# PS.net
KiCad netlist of a schematic drawn in EAGLE
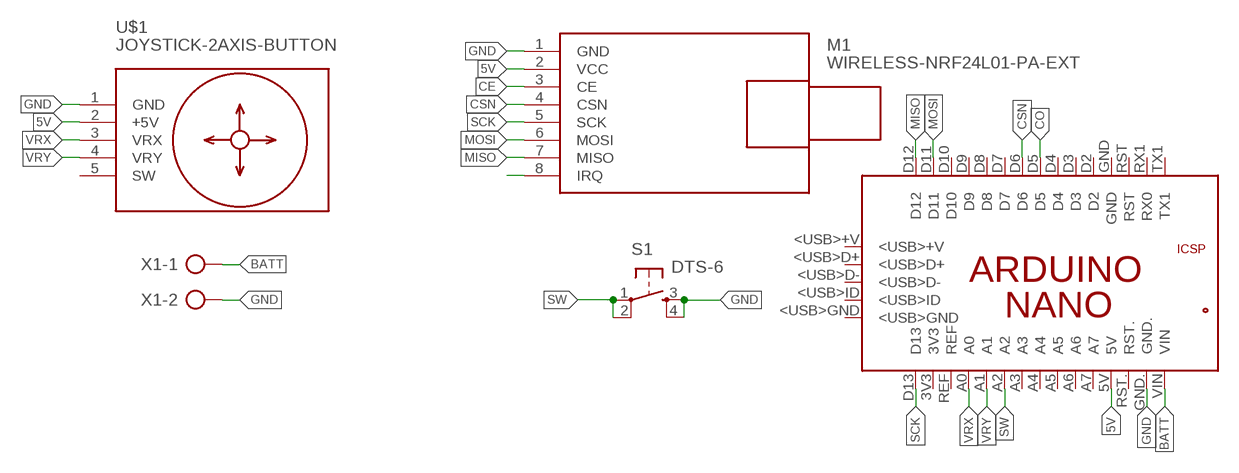
[diagram p0: schematic, sheet 1]

(export (version "E")
  (design (tool "Eeschema 10.0.6"))
  (components
    (comp (ref "M1")
      (value "WIRELESS-NRF24L01-PA-EXT")
      (footprint "eagle-import:WIRELESS-NRF24L01-PA-EXT")
      (libsource (lib "eagle-import") (part "WIRELESS-NRF24L01-PA-EXT"))
    )
    (comp (ref "PCB2")
      (value "ARDUINO_NANO")
      (footprint "eagle-import:ARDUINO_NANO")
      (libsource (lib "eagle-import") (part "ARDUINO_NANO"))
    )
    (comp (ref "S1")
      (value "DTS-6")
      (footprint "eagle-import:DTS-6")
      (libsource (lib "eagle-import") (part "DTS-6"))
    )
    (comp (ref "U$1")
      (value "JOYSTICK-2AXIS-BUTTON")
      (footprint "eagle-import:JOYSTICK-2AXIS-BUTTON")
      (libsource (lib "eagle-import") (part "JOYSTICK-2AXIS-BUTTON"))
    )
    (comp (ref "X1")
      (value "AK300/2")
      (footprint "eagle-import:AK300_2")
      (libsource (lib "eagle-import") (part "AK300/2"))
    )
  )
  (nets
    (net (code "1") (name "5V") (class "Default")
      (node (ref "M1") (pin "2") (pinfunction "VCC_2") (pintype "power_in"))
      (node (ref "PCB2") (pin "5V") (pinfunction "5V_5V") (pintype "bidirectional"))
      (node (ref "U$1") (pin "2") (pinfunction "+5V_2") (pintype "power_in"))
    )
    (net (code "2") (name "BATT") (class "Default")
      (node (ref "PCB2") (pin "VIN") (pinfunction "VIN_VIN") (pintype "bidirectional"))
      (node (ref "X1") (pin "1") (pinfunction "KL_1") (pintype "passive"))
    )
    (net (code "3") (name "CE") (class "Default")
      (node (ref "M1") (pin "3") (pinfunction "CE_3") (pintype "bidirectional"))
    )
    (net (code "4") (name "CO") (class "Default")
      (node (ref "PCB2") (pin "D5") (pinfunction "D5_D5") (pintype "bidirectional"))
    )
    (net (code "5") (name "CSN") (class "Default")
      (node (ref "M1") (pin "4") (pinfunction "CSN_4") (pintype "bidirectional"))
      (node (ref "PCB2") (pin "D6") (pinfunction "D6_D6") (pintype "bidirectional"))
    )
    (net (code "6") (name "GND") (class "Default")
      (node (ref "M1") (pin "1") (pinfunction "GND_1") (pintype "power_in"))
      (node (ref "PCB2") (pin "GND.") (pinfunction "GND._GND.") (pintype "bidirectional"))
      (node (ref "S1") (pin "3") (pinfunction "3_3") (pintype "passive"))
      (node (ref "S1") (pin "4") (pinfunction "4_4") (pintype "passive"))
      (node (ref "U$1") (pin "1") (pinfunction "GND_1") (pintype "power_in"))
      (node (ref "X1") (pin "2") (pinfunction "KL_2") (pintype "passive"))
    )
    (net (code "7") (name "MISO") (class "Default")
      (node (ref "M1") (pin "7") (pinfunction "MISO_7") (pintype "bidirectional"))
      (node (ref "PCB2") (pin "D12") (pinfunction "D12_D12") (pintype "bidirectional"))
    )
    (net (code "8") (name "MOSI") (class "Default")
      (node (ref "M1") (pin "6") (pinfunction "MOSI_6") (pintype "bidirectional"))
      (node (ref "PCB2") (pin "D11") (pinfunction "D11_D11") (pintype "bidirectional"))
    )
    (net (code "9") (name "SCK") (class "Default")
      (node (ref "M1") (pin "5") (pinfunction "SCK_5") (pintype "bidirectional"))
      (node (ref "PCB2") (pin "D13") (pinfunction "D13_D13") (pintype "bidirectional"))
    )
    (net (code "10") (name "SW") (class "Default")
      (node (ref "PCB2") (pin "A2") (pinfunction "A2_A2") (pintype "bidirectional"))
      (node (ref "S1") (pin "1") (pinfunction "1_1") (pintype "passive"))
      (node (ref "S1") (pin "2") (pinfunction "2_2") (pintype "passive"))
    )
    (net (code "11") (name "VRX") (class "Default")
      (node (ref "PCB2") (pin "A0") (pinfunction "A0_A0") (pintype "bidirectional"))
      (node (ref "U$1") (pin "3") (pinfunction "VRX_3") (pintype "passive"))
    )
    (net (code "12") (name "VRY") (class "Default")
      (node (ref "PCB2") (pin "A1") (pinfunction "A1_A1") (pintype "bidirectional"))
      (node (ref "U$1") (pin "4") (pinfunction "VRY_4") (pintype "passive"))
    )
    (net (code "13") (name "unconnected-(M1-IRQ-Pad8)") (class "Default")
      (node (ref "M1") (pin "8") (pinfunction "IRQ_8") (pintype "bidirectional"))
    )
    (net (code "14") (name "unconnected-(PCB2-Pad3V3)") (class "Default")
      (node (ref "PCB2") (pin "3V3") (pinfunction "3V3_3V3") (pintype "bidirectional"))
    )
    (net (code "15") (name "unconnected-(PCB2-Pad5V.)") (class "Default")
      (node (ref "PCB2") (pin "5V.") (pinfunction "5V._5V.") (pintype "bidirectional"))
    )
    (net (code "16") (name "unconnected-(PCB2-Pad<USB>+V)") (class "Default")
      (node (ref "PCB2") (pin "<USB>+V") (pinfunction "<USB>+V_<USB>+V") (pintype "bidirectional"))
    )
    (net (code "17") (name "unconnected-(PCB2-Pad<USB>D+)") (class "Default")
      (node (ref "PCB2") (pin "<USB>D+") (pinfunction "<USB>D+_<USB>D+") (pintype "bidirectional"))
    )
    (net (code "18") (name "unconnected-(PCB2-Pad<USB>D-)") (class "Default")
      (node (ref "PCB2") (pin "<USB>D-") (pinfunction "<USB>D-_<USB>D-") (pintype "bidirectional"))
    )
    (net (code "19") (name "unconnected-(PCB2-Pad<USB>GND)") (class "Default")
      (node (ref "PCB2") (pin "<USB>GND") (pinfunction "<USB>GND_<USB>GND") (pintype "bidirectional"))
    )
    (net (code "20") (name "unconnected-(PCB2-Pad<USB>ID)") (class "Default")
      (node (ref "PCB2") (pin "<USB>ID") (pinfunction "<USB>ID_<USB>ID") (pintype "bidirectional"))
    )
    (net (code "21") (name "unconnected-(PCB2-PadA3)") (class "Default")
      (node (ref "PCB2") (pin "A3") (pinfunction "A3_A3") (pintype "bidirectional"))
    )
    (net (code "22") (name "unconnected-(PCB2-PadA4)") (class "Default")
      (node (ref "PCB2") (pin "A4") (pinfunction "A4_A4") (pintype "bidirectional"))
    )
    (net (code "23") (name "unconnected-(PCB2-PadA5)") (class "Default")
      (node (ref "PCB2") (pin "A5") (pinfunction "A5_A5") (pintype "bidirectional"))
    )
    (net (code "24") (name "unconnected-(PCB2-PadA6)") (class "Default")
      (node (ref "PCB2") (pin "A6") (pinfunction "A6_A6") (pintype "bidirectional"))
    )
    (net (code "25") (name "unconnected-(PCB2-PadA7)") (class "Default")
      (node (ref "PCB2") (pin "A7") (pinfunction "A7_A7") (pintype "bidirectional"))
    )
    (net (code "26") (name "unconnected-(PCB2-PadD2)") (class "Default")
      (node (ref "PCB2") (pin "D2") (pinfunction "D2_D2") (pintype "bidirectional"))
    )
    (net (code "27") (name "unconnected-(PCB2-PadD3)") (class "Default")
      (node (ref "PCB2") (pin "D3") (pinfunction "D3_D3") (pintype "bidirectional"))
    )
    (net (code "28") (name "unconnected-(PCB2-PadD4)") (class "Default")
      (node (ref "PCB2") (pin "D4") (pinfunction "D4_D4") (pintype "bidirectional"))
    )
    (net (code "29") (name "unconnected-(PCB2-PadD7)") (class "Default")
      (node (ref "PCB2") (pin "D7") (pinfunction "D7_D7") (pintype "bidirectional"))
    )
    (net (code "30") (name "unconnected-(PCB2-PadD8)") (class "Default")
      (node (ref "PCB2") (pin "D8") (pinfunction "D8_D8") (pintype "bidirectional"))
    )
    (net (code "31") (name "unconnected-(PCB2-PadD9)") (class "Default")
      (node (ref "PCB2") (pin "D9") (pinfunction "D9_D9") (pintype "bidirectional"))
    )
    (net (code "32") (name "unconnected-(PCB2-PadD10)") (class "Default")
      (node (ref "PCB2") (pin "D10") (pinfunction "D10_D10") (pintype "bidirectional"))
    )
    (net (code "33") (name "unconnected-(PCB2-PadGND)") (class "Default")
      (node (ref "PCB2") (pin "GND") (pinfunction "GND_GND") (pintype "bidirectional"))
    )
    (net (code "34") (name "unconnected-(PCB2-PadGND_)") (class "Default")
      (node (ref "PCB2") (pin "GND_") (pinfunction "GND__GND_") (pintype "bidirectional"))
    )
    (net (code "35") (name "unconnected-(PCB2-PadMISO)") (class "Default")
      (node (ref "PCB2") (pin "MISO") (pinfunction "MISO_MISO") (pintype "bidirectional"))
    )
    (net (code "36") (name "unconnected-(PCB2-PadMOSI)") (class "Default")
      (node (ref "PCB2") (pin "MOSI") (pinfunction "MOSI_MOSI") (pintype "bidirectional"))
    )
    (net (code "37") (name "unconnected-(PCB2-PadREF)") (class "Default")
      (node (ref "PCB2") (pin "REF") (pinfunction "REF_REF") (pintype "bidirectional"))
    )
    (net (code "38") (name "unconnected-(PCB2-PadRESET..)") (class "Default")
      (node (ref "PCB2") (pin "RESET..") (pinfunction "RESET.._RESET..") (pintype "bidirectional"))
    )
    (net (code "39") (name "unconnected-(PCB2-PadRST)") (class "Default")
      (node (ref "PCB2") (pin "RST") (pinfunction "RST_RST") (pintype "bidirectional"))
    )
    (net (code "40") (name "unconnected-(PCB2-PadRST.)") (class "Default")
      (node (ref "PCB2") (pin "RST.") (pinfunction "RST._RST.") (pintype "bidirectional"))
    )
    (net (code "41") (name "unconnected-(PCB2-PadSCK)") (class "Default")
      (node (ref "PCB2") (pin "SCK") (pinfunction "SCK_SCK") (pintype "bidirectional"))
    )
    (net (code "42") (name "unconnected-(PCB2-PadTX1)") (class "Default")
      (node (ref "PCB2") (pin "TX1") (pinfunction "TX1_TX1") (pintype "bidirectional"))
    )
    (net (code "43") (name "unconnected-(PCB2-RX0-PadRX1)") (class "Default")
      (node (ref "PCB2") (pin "RX1") (pinfunction "RX0_RX1") (pintype "bidirectional"))
    )
    (net (code "44") (name "unconnected-(U$1-SW-Pad5)") (class "Default")
      (node (ref "U$1") (pin "5") (pinfunction "SW_5") (pintype "passive"))
    )
  )
)
